# Power.net
KiCad netlist of a schematic drawn in Altium Designer
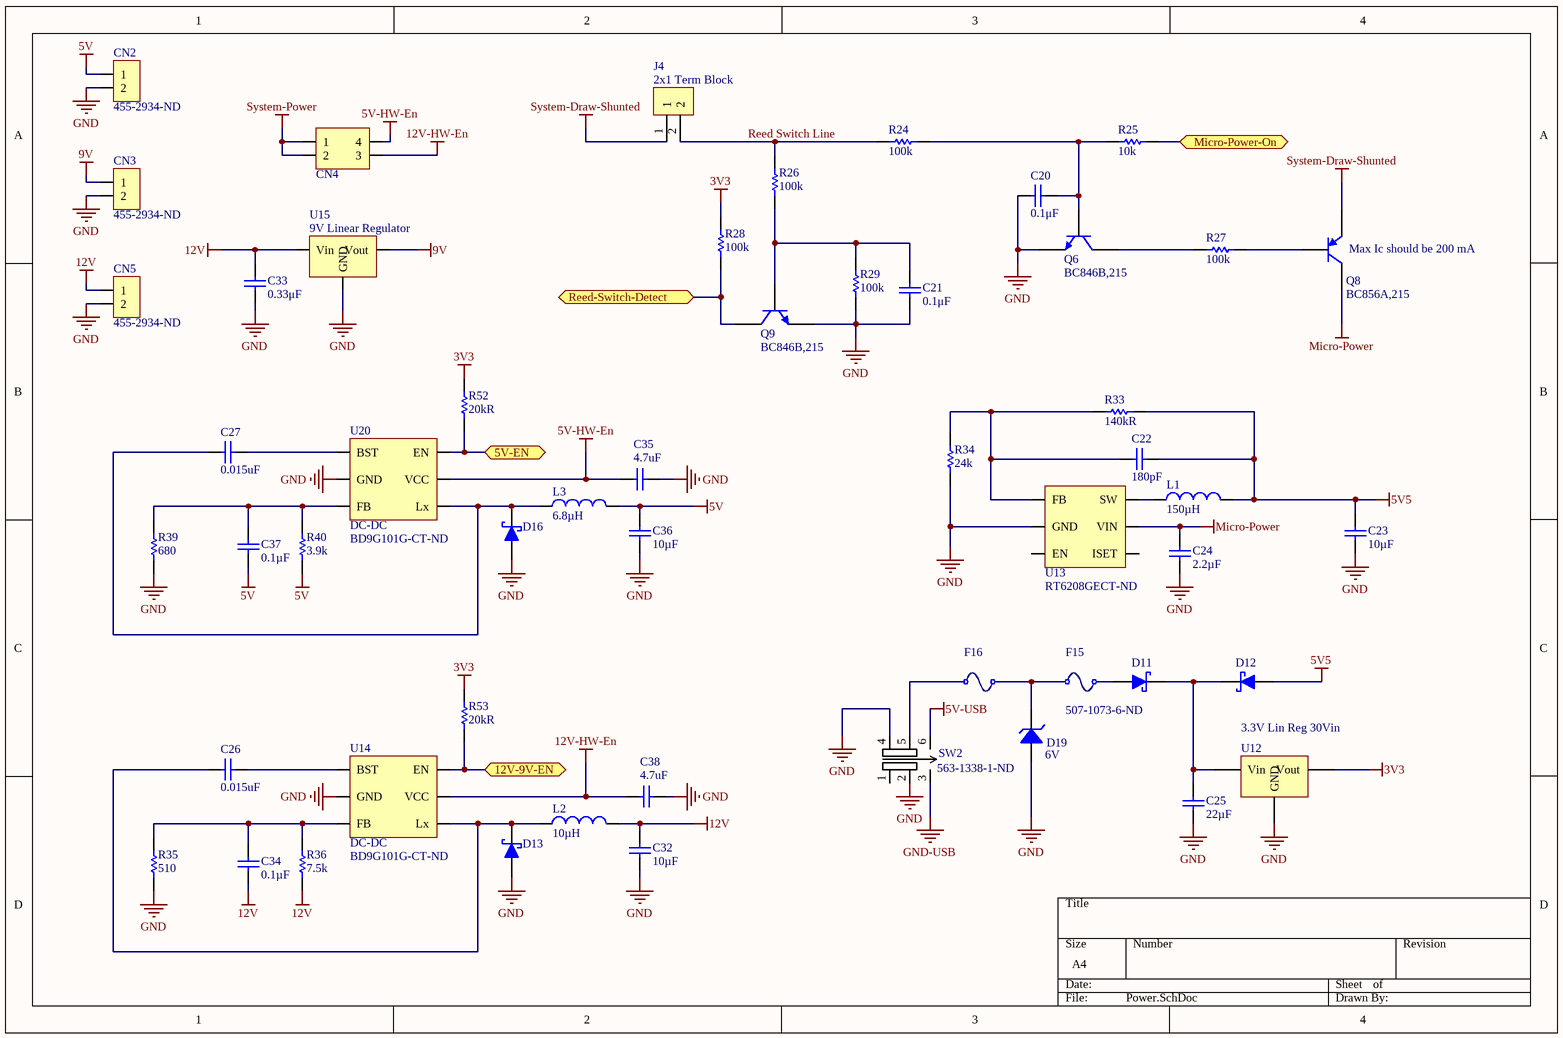
[diagram p0: Power.SchDoc]

(export (version "E")
  (design (tool "Eeschema 10.0.6"))
  (components
    (comp (ref "C20")
      (value "0.1μF")
      (footprint "CAPC1608N(0603\")")
      (description "Capacitor, Ceramic, 100V, +/- 10%, 0603 SMD, X7R")
      (fields
        (field (name "MFG") "TDK")
        (field (name "PUBLISHER") "AUVic")
        (field (name "CREATED BY") "Ashwin Sira")
      )
      (libsource (lib "AUVic_Integrated_Library_Capacitors") (part "0.1uF 100V 0603 SMD, Ceramic"))
    )
    (comp (ref "C21")
      (value "0.1μF")
      (footprint "CAPC1608N(0603\")")
      (description "Capacitor, Ceramic, 100V, +/- 10%, 0603 SMD, X7R")
      (fields
        (field (name "MFG") "TDK")
        (field (name "PUBLISHER") "AUVic")
        (field (name "CREATED BY") "Ashwin Sira")
      )
      (libsource (lib "AUVic_Integrated_Library_Capacitors") (part "0.1uF 100V 0603 SMD, Ceramic"))
    )
    (comp (ref "C22")
      (value "180pF")
      (footprint "CAPC1608N(0603\")")
      (description "Capacitor, Ceramic, 50V, +/-5%, 0603 SMD, NP0")
      (fields (field (name "CREATED BY") "Lyden Smith"))
      (libsource (lib "AUVic_Integrated_Library_Capacitors") (part "180pF 50V 0603 SMD, Ceramic"))
    )
    (comp (ref "C23")
      (value "10µF")
      (footprint "CAPC2012N(0805\")")
      (description "Capacitor, Ceramic, 10V, +/- 10%, 0805 SMD, X5R")
      (fields (field (name "PUBLISHER") "AUVic") (field (name "MADE BY") "Andy Bates"))
      (libsource (lib "AUVic_Integrated_Library_Capacitors") (part "10uF 10V 0805 SMD, Ceramic"))
    )
    (comp (ref "C24")
      (value "2.2µF")
      (footprint "CAPC1608N(0603\")")
      (description "Capacitor, Ceramic, 50V, 10%, 0603 SMD, X5R")
      (fields (field (name "MADE BY") "*") (field (name "PUBLISHER") "AUVic"))
      (libsource (lib "AUVic_Integrated_Library_Capacitors") (part "2.2uF, 50V, 0603 SMD, X5R, Ceramic"))
    )
    (comp (ref "C25")
      (value "22µF")
      (footprint "CAPC2012N(0805\")")
      (description "Capacitor, Ceramic, 35V, +/- 20%, 0805 SMD, X5R")
      (fields (field (name "PUBLISHER") "AUVic"))
      (libsource (lib "AUVic_Integrated_Library_Capacitors") (part "22uF 35V 0805 SMD, Ceramic"))
    )
    (comp (ref "C26")
      (value "0.015uF")
      (footprint "CAPC1608N(0603\")")
      (description "Capacitor, Ceramic, 50V, +/-10%, 0603 SMD, X7R")
      (fields (field (name "CREATED BY") "Lyden Smith"))
      (libsource (lib "AUVic_Integrated_Library_Capacitors") (part "0.015uF 50V 0603 SMD, Ceramic"))
    )
    (comp (ref "C27")
      (value "0.015uF")
      (footprint "CAPC1608N(0603\")")
      (description "Capacitor, Ceramic, 50V, +/-10%, 0603 SMD, X7R")
      (fields (field (name "CREATED BY") "Lyden Smith"))
      (libsource (lib "AUVic_Integrated_Library_Capacitors") (part "0.015uF 50V 0603 SMD, Ceramic"))
    )
    (comp (ref "C32")
      (value "10µF")
      (footprint "CAPC3216N(1206\")")
      (description "Capacitor, Ceramic, 50V, +/- 10%, 1206 SMD, X5R")
      (fields (field (name "PUBLISHER") "AUVic"))
      (libsource (lib "AUVic_Integrated_Library_Capacitors") (part "10uF 50V 1206 SMD, Ceramic"))
    )
    (comp (ref "C33")
      (value "0.33μF")
      (footprint "CAPC1608N(0603\")")
      (description "Capacitor, Ceramic, 50V, +/- 10%, 0603 SMD, X5R")
      (fields
        (field (name "MFG") "TDK")
        (field (name "PUBLISHER") "AUVic")
        (field (name "CREATED BY") "Andy Bates")
      )
      (libsource (lib "AUVic_Integrated_Library_Capacitors") (part "0.33uF 50V 0603 SMD, Ceramic"))
    )
    (comp (ref "C34")
      (value "0.1uF, 50V, 10%, X7R, 1608")
      (footprint "CAPC1608N(0603\")")
      (description "CAP CER 0.1UF 50V 10% X7R 1608 (0603)")
      (fields
        (field (name "MANUFACTURER") "Samsung Electro-Mechanics America, Inc")
        (field (name "MANUFACTURER PART NUMBER") "CL10B104KB8SFNC")
        (field (name "CAPACITANCE") "0.1µF")
      )
      (libsource (lib "AUVic_Integrated_Library_Capacitors") (part "0.1uF, 50V, 10%, X7R, 1608"))
    )
    (comp (ref "C35")
      (value "4.7uF")
      (footprint "CAPC3216N(1206\")")
      (description "Capacitor, Ceramic, 50V, +/- 10%, 1206 SMD, X7R")
      (fields (field (name "CREATED BY") "Lyden Smith"))
      (libsource (lib "AUVic_Integrated_Library_Capacitors") (part "4.7uF 50V 1206 SMD, Ceramic"))
    )
    (comp (ref "C36")
      (value "10µF")
      (footprint "CAPC2012N(0805\")")
      (description "Capacitor, Ceramic, 10V, +/- 10%, 0805 SMD, X5R")
      (fields (field (name "PUBLISHER") "AUVic") (field (name "MADE BY") "Andy Bates"))
      (libsource (lib "") (part "10uF 10V 0805 SMD, Ceramic_1"))
    )
    (comp (ref "C37")
      (value "0.1uF, 50V, 10%, X7R, 1608")
      (footprint "CAPC1608N(0603\")")
      (description "CAP CER 0.1UF 50V 10% X7R 1608 (0603)")
      (fields
        (field (name "MANUFACTURER") "Samsung Electro-Mechanics America, Inc")
        (field (name "MANUFACTURER PART NUMBER") "CL10B104KB8SFNC")
        (field (name "CAPACITANCE") "0.1µF")
      )
      (libsource (lib "AUVic_Integrated_Library_Capacitors") (part "0.1uF, 50V, 10%, X7R, 1608"))
    )
    (comp (ref "C38")
      (value "4.7uF")
      (footprint "CAPC3216N(1206\")")
      (description "Capacitor, Ceramic, 50V, +/- 10%, 1206 SMD, X7R")
      (fields (field (name "CREATED BY") "Lyden Smith"))
      (libsource (lib "AUVic_Integrated_Library_Capacitors") (part "4.7uF 50V 1206 SMD, Ceramic"))
    )
    (comp (ref "CN2")
      (value "1x2, JST B2B-EH-A, Pads Pitch: 0.098\" (2.50mm), Through Hole")
      (footprint "Male JST B2B-EH-A")
      (fields (field (name "SUPPLIER PART NUMBER 1") "455-2934-ND") (field (name "CREATED BY") "Lyden Smith"))
      (libsource (lib "AUVic_Integrated_Library_Connectors") (part "1x2, JST B2B-EH-A, Pads Pitch{colon} 0.098{dblquote} (2.50mm), Through Hole"))
    )
    (comp (ref "CN3")
      (value "1x2, JST B2B-EH-A, Pads Pitch: 0.098\" (2.50mm), Through Hole")
      (footprint "Male JST B2B-EH-A")
      (fields (field (name "SUPPLIER PART NUMBER 1") "455-2934-ND") (field (name "CREATED BY") "Lyden Smith"))
      (libsource (lib "AUVic_Integrated_Library_Connectors") (part "1x2, JST B2B-EH-A, Pads Pitch{colon} 0.098{dblquote} (2.50mm), Through Hole"))
    )
    (comp (ref "CN4")
      (value "Header, Male, 2x2, Pitch: 0.1\" (2.54mm), THT")
      (footprint "Header, Male, 2x2, Pitch: 0.1\" (2.54mm),THT")
      (fields
        (field (name "PUBLISHER") "AUVic")
        (field (name "REVIEWED BY") "*")
        (field (name "CREATED BY") "Lyden Smith")
      )
      (libsource (lib "AUVic_Integrated_Library_Connectors") (part "Header, Male, 2x2, Pitch{colon} 0.1{dblquote} (2.54mm), THT"))
    )
    (comp (ref "CN5")
      (value "1x2, JST B2B-EH-A, Pads Pitch: 0.098\" (2.50mm), Through Hole")
      (footprint "Male JST B2B-EH-A")
      (fields (field (name "SUPPLIER PART NUMBER 1") "455-2934-ND") (field (name "CREATED BY") "Lyden Smith"))
      (libsource (lib "AUVic_Integrated_Library_Connectors") (part "1x2, JST B2B-EH-A, Pads Pitch{colon} 0.098{dblquote} (2.50mm), Through Hole"))
    )
    (comp (ref "D11")
      (value "CUS08F30H3FCT-ND")
      (footprint "SC-76")
      (description "Diode, Schottky, 30V, 800mA")
      (fields (field (name "CREATED BY") "Andy Bates") (field (name "PUBLISHER") "AUVic"))
      (libsource (lib "AUVic_Integrated_Library_Diodes") (part "CUS08F30H3FCT-ND"))
    )
    (comp (ref "D12")
      (value "CUS08F30H3FCT-ND")
      (footprint "SC-76")
      (description "Diode, Schottky, 30V, 800mA")
      (fields (field (name "CREATED BY") "Andy Bates") (field (name "PUBLISHER") "AUVic"))
      (libsource (lib "AUVic_Integrated_Library_Diodes") (part "CUS08F30H3FCT-ND"))
    )
    (comp (ref "D13")
      (value "RB060M-60TR")
      (footprint "SOD-123")
      (description "Diode, Schottky, 60V, 2A")
      (fields (field (name "CREATED BY") "Lyden Smith"))
      (libsource (lib "AUVic_Integrated_Library_Diodes") (part "RB060M-60TR"))
    )
    (comp (ref "D16")
      (value "RB060M-60TR")
      (footprint "SOD-123")
      (description "Diode, Schottky, 60V, 2A")
      (fields (field (name "CREATED BY") "Lyden Smith"))
      (libsource (lib "AUVic_Integrated_Library_Diodes") (part "RB060M-60TR"))
    )
    (comp (ref "D19")
      (value "6V")
      (footprint "DO-214AA")
      (description "DIODE ZENER 6V 5W DO214AA")
      (fields (field (name "CREATED BY") "Lyden Smith"))
      (libsource (lib "AUVic_Integrated_Library_Diodes") (part "SMBJ5340B-TPMSCT-ND"))
    )
    (comp (ref "F15")
      (value "SMD")
      (footprint "1206 SMD")
      (description "SMD Fuse, 250mA, 63V, 1206")
      (fields
        (field (name "SUPPLIER PART NUMBER 1") "507-1073-6-ND")
        (field (name "CREATED BY") "Lyden Smith")
      )
      (libsource (lib "AUVic_Integrated_Library_Fuses") (part "SMD Fuse, 250mA, 63V, 1206"))
    )
    (comp (ref "F16")
      (value "SMD")
      (footprint "1206 SMD")
      (description "SMD Fuse, 250mA, 63V, 1206")
      (fields (field (name "CREATED BY") "Lyden Smith"))
      (libsource (lib "AUVic_Integrated_Library_Fuses") (part "SMD Fuse, 250mA, 63V, 1206"))
    )
    (comp (ref "J4")
      (value "2x1 Term Block")
      (footprint "2X1 Terminal Blocks")
      (fields (field (name "MADE BY") "Andy Bates"))
      (libsource (lib "AUVic_Integrated_Library_Connectors") (part "2x1 Terminal Block"))
    )
    (comp (ref "L1")
      (value "150µH")
      (footprint "CB - 1007 (2518)")
      (description "150µH 210mA 4.6Ohm")
      (fields (field (name "CREATED BY") "Lyden Smith"))
      (libsource (lib "AUVic_Integrated_Library_Inductors") (part "CB2518T151K"))
    )
    (comp (ref "L2")
      (value "10µH")
      (footprint "NR4018T6R8M Inductor")
      (description "10uH 840mA")
      (fields (field (name "CREATED BY") "Lyden Smith"))
      (libsource (lib "AUVic_Integrated_Library_Inductors") (part "NR4018T100M"))
    )
    (comp (ref "L3")
      (value "6.8µH")
      (footprint "NR4018T6R8M Inductor")
      (description "6.8uH 1.06A")
      (fields (field (name "CREATED BY") "Lyden Smith"))
      (libsource (lib "AUVic_Integrated_Library_Inductors") (part "NR4018T6R8M"))
    )
    (comp (ref "Q6")
      (value "BC846B,215")
      (footprint "SOT-23")
      (description "NPN 65V 100mA 250mW")
      (fields (field (name "PUBLISHER") "Andy Bates"))
      (libsource (lib "AUVic_Integrated_Library_Transistors") (part "BC846B,215"))
    )
    (comp (ref "Q8")
      (value "BC856A,215")
      (footprint "SOT-23")
      (description "PNP 65V 100mA 250mW")
      (libsource (lib "AUVic_Integrated_Library_Transistors") (part "BC856A,215"))
    )
    (comp (ref "Q9")
      (value "BC846B,215")
      (footprint "SOT-23")
      (description "NPN 65V 100mA 250mW")
      (fields (field (name "PUBLISHER") "Andy Bates"))
      (libsource (lib "AUVic_Integrated_Library_Transistors") (part "BC846B,215"))
    )
    (comp (ref "R24")
      (value "100k")
      (footprint "RESC1608N(0603\")")
      (description "100kR, 1%, 1/10W, 0603 SMD")
      (fields (field (name "MADE BY") "Andy Bates"))
      (libsource (lib "AUVic_Integrated_Library_Resistors") (part "100kR, 1%, 1/10W, 0603 SMD"))
    )
    (comp (ref "R25")
      (value "10k")
      (footprint "RESC1608N(0603\")")
      (description "10kR, 1%, 1/10W, 0603 SMD")
      (fields (field (name "MADE BY") "Ashwin Sira"))
      (libsource (lib "AUVic_Integrated_Library_Resistors") (part "10kR, 1%, 1/10W, 0603 SMD"))
    )
    (comp (ref "R26")
      (value "100k")
      (footprint "RESC1608N(0603\")")
      (description "100kR, 1%, 1/10W, 0603 SMD")
      (fields (field (name "MADE BY") "Andy Bates"))
      (libsource (lib "AUVic_Integrated_Library_Resistors") (part "100kR, 1%, 1/10W, 0603 SMD"))
    )
    (comp (ref "R27")
      (value "100k")
      (footprint "RESC1608N(0603\")")
      (description "100kR, 1%, 1/10W, 0603 SMD")
      (fields (field (name "MADE BY") "Andy Bates"))
      (libsource (lib "AUVic_Integrated_Library_Resistors") (part "100kR, 1%, 1/10W, 0603 SMD"))
    )
    (comp (ref "R28")
      (value "100k")
      (footprint "RESC1608N(0603\")")
      (description "100kR, 1%, 1/10W, 0603 SMD")
      (fields (field (name "MADE BY") "Andy Bates"))
      (libsource (lib "AUVic_Integrated_Library_Resistors") (part "100kR, 1%, 1/10W, 0603 SMD"))
    )
    (comp (ref "R29")
      (value "100k")
      (footprint "RESC1608N(0603\")")
      (description "100kR, 1%, 1/10W, 0603 SMD")
      (fields (field (name "MADE BY") "Andy Bates"))
      (libsource (lib "AUVic_Integrated_Library_Resistors") (part "100kR, 1%, 1/10W, 0603 SMD"))
    )
    (comp (ref "R33")
      (value "140kR")
      (footprint "RESC1005N(0402\")")
      (description "140kR, 1%, 1/16W, 0402, SMD")
      (fields (field (name "CREATED BY") "Lyden Smith") (field (name "PUBLISHER") "AUVic"))
      (libsource (lib "AUVic_Integrated_Library_Resistors") (part "140kR, 1%, 1/16W, 0402, SMD"))
    )
    (comp (ref "R34")
      (value "24k")
      (footprint "RESC2012N(0805\")")
      (description "24k, 5%, 1/8W, 0805 SMD")
      (fields (field (name "CREATED BY") "Lyden Smith"))
      (libsource (lib "AUVic_Integrated_Library_Resistors") (part "24k, 5%, 1/8W, 0805 SMD"))
    )
    (comp (ref "R35")
      (value "510")
      (footprint "RESC2012N(0805\")")
      (description "510, 5%, 1/8W, 0805 SMD")
      (fields (field (name "CREATED BY") "Lyden Smith"))
      (libsource (lib "AUVic_Integrated_Library_Resistors") (part "510, 5%, 1/8W, 0805 SMD"))
    )
    (comp (ref "R36")
      (value "7.5k")
      (footprint "RESC2012N(0805\")")
      (description "7.5k, 5%, 1/8W, 0805 SMD")
      (fields (field (name "CREATED BY") "Lyden Smith"))
      (libsource (lib "AUVic_Schematic_Library_Resistors") (part "7.5k, 5%, 1/8W, 0805 SMD"))
    )
    (comp (ref "R39")
      (value "680")
      (footprint "RESC2012N(0805\")")
      (description "680, 5%, 1/8W, 0805 SMD")
      (fields (field (name "CREATED BY") "Lyden Smith"))
      (libsource (lib "AUVic_Integrated_Library_Resistors") (part "680, 5%, 1/8W, 0805 SMD"))
    )
    (comp (ref "R40")
      (value "3.9k")
      (footprint "RESC2012N(0805\")")
      (description "3.9k, 5%, 1/8W, 0805 SMD")
      (fields (field (name "CREATED BY") "Lyden Smith"))
      (libsource (lib "AUVic_Integrated_Library_Resistors") (part "3.9k, 5%, 1/8W, 0805 SMD"))
    )
    (comp (ref "R52")
      (value "20kR")
      (footprint "RESC1608N(0603\")")
      (description "20k, 1%, 1/10W, 0603, SMD")
      (fields (field (name "CREATED BY") "Andy Bates") (field (name "PUBLISHER") "AUVic"))
      (libsource (lib "AUVic_Integrated_Library_Resistors") (part "20k, 1%, 1/10W, 0603, SMD"))
    )
    (comp (ref "R53")
      (value "20kR")
      (footprint "RESC1608N(0603\")")
      (description "20k, 1%, 1/10W, 0603, SMD")
      (fields (field (name "CREATED BY") "Andy Bates") (field (name "PUBLISHER") "AUVic"))
      (libsource (lib "AUVic_Integrated_Library_Resistors") (part "20k, 1%, 1/10W, 0603, SMD"))
    )
    (comp (ref "SW2")
      (value "*")
      (footprint "CL-2B-22A")
      (description "DPDT, 12V, 200mA, SMT")
      (fields
        (field (name "SUPPLIER PART NUMBER 1") "563-1338-1-ND")
        (field (name "CREATED BY") "Lyden Smith")
      )
      (libsource (lib "AUVic_Integrated_Library_Switches") (part "DPDT, 12V, 200mA, SMT"))
    )
    (comp (ref "U12")
      (value "3.3V Lin Reg 30Vin")
      (footprint "T0-252")
      (libsource (lib "AUVic_Integrated_Library_Regulators") (part "3.3V TO-252 Linear Regulator"))
    )
    (comp (ref "U13")
      (value "RT6208GE")
      (footprint "SOT23-6_L")
      (description "Adjustable Buck, 100mA, SOT-23")
      (fields
        (field (name "SUPPLIER PART NUMBER 1") "RT6208GECT-ND")
        (field (name "CREATED BY") "Lyden Smith")
      )
      (libsource (lib "AUVic_Integrated_Library_Regulators") (part "RT6208GE"))
    )
    (comp (ref "U14")
      (value "DC-DC")
      (footprint "SOT23-6_L")
      (description "DC-DC Regulator, 6V-42V in, 1V-29.4V out, 500mA")
      (fields (field (name "SUPPLIER PART NUMBER 1") "BD9G101G-CT-ND"))
      (libsource (lib "AUVic_Integrated_Library_Regulators") (part "BD9G101G-TR"))
    )
    (comp (ref "U15")
      (value "9V Linear Regulator")
      (footprint "DPAK229P991X238-3N")
      (description "9V Linear Regulator, 500mA")
      (fields (field (name "CREATED BY") "Lyden Smith"))
      (libsource (lib "AUVic_Integrated_Library_Regulators") (part "MC78M09CDTRKG"))
    )
    (comp (ref "U20")
      (value "DC-DC")
      (footprint "SOT23-6_L")
      (description "DC-DC Regulator, 6V-42V in, 1V-29.4V out, 500mA")
      (fields (field (name "SUPPLIER PART NUMBER 1") "BD9G101G-CT-ND"))
      (libsource (lib "AUVic_Integrated_Library_Regulators") (part "BD9G101G-TR"))
    )
  )
  (nets
    (net (code "1") (name "/5V-EN") (class "Default")
      (node (ref "R52") (pin "1") (pinfunction "1_1") (pintype "passive"))
      (node (ref "U20") (pin "4") (pinfunction "EN_4") (pintype "passive"))
    )
    (net (code "2") (name "/12V-9V-EN") (class "Default")
      (node (ref "R53") (pin "1") (pinfunction "1_1") (pintype "passive"))
      (node (ref "U14") (pin "4") (pinfunction "EN_4") (pintype "passive"))
    )
    (net (code "3") (name "/Micro-Power-On") (class "Default")
      (node (ref "R25") (pin "2") (pinfunction "2_2") (pintype "passive"))
    )
    (net (code "4") (name "/Reed Switch Line") (class "Default")
      (node (ref "J4") (pin "2") (pinfunction "2_2") (pintype "passive"))
      (node (ref "R24") (pin "2") (pinfunction "2_2") (pintype "passive"))
      (node (ref "R26") (pin "2") (pinfunction "2_2") (pintype "passive"))
    )
    (net (code "5") (name "/Reed-Switch-Detect") (class "Default")
      (node (ref "Q9") (pin "3") (pinfunction "C_3") (pintype "passive"))
      (node (ref "R28") (pin "1") (pinfunction "1_1") (pintype "passive"))
    )
    (net (code "6") (name "3V3") (class "Default")
      (node (ref "R28") (pin "2") (pinfunction "2_2") (pintype "passive"))
      (node (ref "R52") (pin "2") (pinfunction "2_2") (pintype "passive"))
      (node (ref "R53") (pin "2") (pinfunction "2_2") (pintype "passive"))
      (node (ref "U12") (pin "3") (pinfunction "Vout_3") (pintype "passive"))
    )
    (net (code "7") (name "5V") (class "Default")
      (node (ref "C36") (pin "2") (pinfunction "Cathode_2") (pintype "passive"))
      (node (ref "C37") (pin "1") (pinfunction "Anode_1") (pintype "passive"))
      (node (ref "CN2") (pin "1") (pinfunction "1_1") (pintype "passive"))
      (node (ref "L3") (pin "2") (pinfunction "2_2") (pintype "passive"))
      (node (ref "R40") (pin "1") (pinfunction "1_1") (pintype "passive"))
    )
    (net (code "8") (name "5V-HW-En") (class "Default")
      (node (ref "C35") (pin "2") (pinfunction "2_2") (pintype "passive"))
      (node (ref "CN4") (pin "4") (pinfunction "4_4") (pintype "passive"))
      (node (ref "U20") (pin "5") (pinfunction "VCC_5") (pintype "power_in"))
    )
    (net (code "9") (name "5V-USB") (class "Default")
      (node (ref "SW2") (pin "6") (pinfunction "6_6") (pintype "passive"))
    )
    (net (code "10") (name "5V5") (class "Default")
      (node (ref "C22") (pin "2") (pinfunction "2_2") (pintype "passive"))
      (node (ref "C23") (pin "2") (pinfunction "Cathode_2") (pintype "passive"))
      (node (ref "D12") (pin "A") (pinfunction "Anode_A") (pintype "passive"))
      (node (ref "L1") (pin "2") (pinfunction "2_2") (pintype "passive"))
      (node (ref "R33") (pin "2") (pinfunction "2_2") (pintype "passive"))
    )
    (net (code "11") (name "9V") (class "Default")
      (node (ref "CN3") (pin "1") (pinfunction "1_1") (pintype "passive"))
      (node (ref "U15") (pin "3") (pinfunction "Vout_3") (pintype "passive"))
    )
    (net (code "12") (name "12V") (class "Default")
      (node (ref "C32") (pin "2") (pinfunction "Cathode_2") (pintype "passive"))
      (node (ref "C33") (pin "2") (pinfunction "Cathode_2") (pintype "passive"))
      (node (ref "C34") (pin "1") (pinfunction "Anode_1") (pintype "passive"))
      (node (ref "CN5") (pin "1") (pinfunction "1_1") (pintype "passive"))
      (node (ref "L2") (pin "2") (pinfunction "2_2") (pintype "passive"))
      (node (ref "R36") (pin "1") (pinfunction "1_1") (pintype "passive"))
      (node (ref "U15") (pin "1") (pinfunction "Vin_1") (pintype "passive"))
    )
    (net (code "13") (name "12V-HW-En") (class "Default")
      (node (ref "C38") (pin "2") (pinfunction "2_2") (pintype "passive"))
      (node (ref "CN4") (pin "3") (pinfunction "3_3") (pintype "passive"))
      (node (ref "U14") (pin "5") (pinfunction "VCC_5") (pintype "power_in"))
    )
    (net (code "14") (name "GND") (class "Default")
      (node (ref "C20") (pin "1") (pinfunction "Anode_1") (pintype "passive"))
      (node (ref "C21") (pin "1") (pinfunction "Anode_1") (pintype "passive"))
      (node (ref "C23") (pin "1") (pinfunction "Anode_1") (pintype "passive"))
      (node (ref "C24") (pin "1") (pinfunction "Anode_1") (pintype "passive"))
      (node (ref "C25") (pin "1") (pinfunction "Anode_1") (pintype "passive"))
      (node (ref "C32") (pin "1") (pinfunction "Anode_1") (pintype "passive"))
      (node (ref "C33") (pin "1") (pinfunction "Anode_1") (pintype "passive"))
      (node (ref "C35") (pin "1") (pinfunction "1_1") (pintype "passive"))
      (node (ref "C36") (pin "1") (pinfunction "Anode_1") (pintype "passive"))
      (node (ref "C38") (pin "1") (pinfunction "1_1") (pintype "passive"))
      (node (ref "CN2") (pin "2") (pinfunction "2_2") (pintype "passive"))
      (node (ref "CN3") (pin "2") (pinfunction "2_2") (pintype "passive"))
      (node (ref "CN5") (pin "2") (pinfunction "2_2") (pintype "passive"))
      (node (ref "D13") (pin "A") (pinfunction "Anode_A") (pintype "passive"))
      (node (ref "D16") (pin "A") (pinfunction "Anode_A") (pintype "passive"))
      (node (ref "D19") (pin "A") (pinfunction "Anode_A") (pintype "passive"))
      (node (ref "Q6") (pin "2") (pinfunction "E_2") (pintype "passive"))
      (node (ref "Q9") (pin "2") (pinfunction "E_2") (pintype "passive"))
      (node (ref "R29") (pin "1") (pinfunction "1_1") (pintype "passive"))
      (node (ref "R34") (pin "1") (pinfunction "1_1") (pintype "passive"))
      (node (ref "R35") (pin "1") (pinfunction "1_1") (pintype "passive"))
      (node (ref "R39") (pin "1") (pinfunction "1_1") (pintype "passive"))
      (node (ref "SW2") (pin "2") (pinfunction "2_2") (pintype "passive"))
      (node (ref "SW2") (pin "4") (pinfunction "4_4") (pintype "passive"))
      (node (ref "U12") (pin "1") (pinfunction "GND_1") (pintype "passive"))
      (node (ref "U13") (pin "2") (pinfunction "GND_2") (pintype "passive"))
      (node (ref "U14") (pin "2") (pinfunction "GND_2") (pintype "power_in"))
      (node (ref "U15") (pin "4") (pinfunction "GND_4") (pintype "passive"))
      (node (ref "U20") (pin "2") (pinfunction "GND_2") (pintype "power_in"))
    )
    (net (code "15") (name "GND-USB") (class "Default")
      (node (ref "SW2") (pin "3") (pinfunction "3_3") (pintype "passive"))
    )
    (net (code "16") (name "Micro-Power") (class "Default")
      (node (ref "C24") (pin "2") (pinfunction "Cathode_2") (pintype "passive"))
      (node (ref "Q8") (pin "3") (pinfunction "C_3") (pintype "passive"))
      (node (ref "U13") (pin "5") (pinfunction "VIN_5") (pintype "passive"))
    )
    (net (code "17") (name "Net-(C20-Cathode)") (class "Default")
      (node (ref "C20") (pin "2") (pinfunction "Cathode_2") (pintype "passive"))
      (node (ref "Q6") (pin "1") (pinfunction "B_1") (pintype "passive"))
      (node (ref "R24") (pin "1") (pinfunction "1_1") (pintype "passive"))
      (node (ref "R25") (pin "1") (pinfunction "1_1") (pintype "passive"))
    )
    (net (code "18") (name "Net-(C21-Cathode)") (class "Default")
      (node (ref "C21") (pin "2") (pinfunction "Cathode_2") (pintype "passive"))
      (node (ref "Q9") (pin "1") (pinfunction "B_1") (pintype "passive"))
      (node (ref "R26") (pin "1") (pinfunction "1_1") (pintype "passive"))
      (node (ref "R29") (pin "2") (pinfunction "2_2") (pintype "passive"))
    )
    (net (code "19") (name "Net-(C25-Cathode)") (class "Default")
      (node (ref "C25") (pin "2") (pinfunction "Cathode_2") (pintype "passive"))
      (node (ref "D11") (pin "K") (pinfunction "Cathode_K") (pintype "passive"))
      (node (ref "D12") (pin "K") (pinfunction "Cathode_K") (pintype "passive"))
      (node (ref "U12") (pin "2") (pinfunction "Vin_2") (pintype "passive"))
    )
    (net (code "20") (name "Net-(C34-Cathode)") (class "Default")
      (node (ref "C34") (pin "2") (pinfunction "Cathode_2") (pintype "passive"))
      (node (ref "R35") (pin "2") (pinfunction "2_2") (pintype "passive"))
      (node (ref "R36") (pin "2") (pinfunction "2_2") (pintype "passive"))
      (node (ref "U14") (pin "3") (pinfunction "FB_3") (pintype "power_in"))
    )
    (net (code "21") (name "Net-(C37-Cathode)") (class "Default")
      (node (ref "C37") (pin "2") (pinfunction "Cathode_2") (pintype "passive"))
      (node (ref "R39") (pin "2") (pinfunction "2_2") (pintype "passive"))
      (node (ref "R40") (pin "2") (pinfunction "2_2") (pintype "passive"))
      (node (ref "U20") (pin "3") (pinfunction "FB_3") (pintype "power_in"))
    )
    (net (code "22") (name "Net-(D11-Anode)") (class "Default")
      (node (ref "D11") (pin "A") (pinfunction "Anode_A") (pintype "passive"))
      (node (ref "F15") (pin "2") (pinfunction "2_2") (pintype "passive"))
    )
    (net (code "23") (name "Net-(D13-Cathode)") (class "Default")
      (node (ref "C26") (pin "1") (pinfunction "1_1") (pintype "passive"))
      (node (ref "D13") (pin "K") (pinfunction "Cathode_K") (pintype "passive"))
      (node (ref "L2") (pin "1") (pinfunction "1_1") (pintype "passive"))
      (node (ref "U14") (pin "6") (pinfunction "Lx_6") (pintype "power_in"))
    )
    (net (code "24") (name "Net-(D16-Cathode)") (class "Default")
      (node (ref "C27") (pin "1") (pinfunction "1_1") (pintype "passive"))
      (node (ref "D16") (pin "K") (pinfunction "Cathode_K") (pintype "passive"))
      (node (ref "L3") (pin "1") (pinfunction "1_1") (pintype "passive"))
      (node (ref "U20") (pin "6") (pinfunction "Lx_6") (pintype "power_in"))
    )
    (net (code "25") (name "Net-(D19-Cathode)") (class "Default")
      (node (ref "D19") (pin "K") (pinfunction "Cathode_K") (pintype "passive"))
      (node (ref "F15") (pin "1") (pinfunction "1_1") (pintype "passive"))
      (node (ref "F16") (pin "2") (pinfunction "2_2") (pintype "passive"))
    )
    (net (code "26") (name "Net-(F16-Pad1)") (class "Default")
      (node (ref "F16") (pin "1") (pinfunction "1_1") (pintype "passive"))
      (node (ref "SW2") (pin "5") (pinfunction "5_5") (pintype "passive"))
    )
    (net (code "27") (name "Net-(Q6-C)") (class "Default")
      (node (ref "Q6") (pin "3") (pinfunction "C_3") (pintype "passive"))
      (node (ref "R27") (pin "1") (pinfunction "1_1") (pintype "passive"))
    )
    (net (code "28") (name "Net-(Q8-B)") (class "Default")
      (node (ref "Q8") (pin "1") (pinfunction "B_1") (pintype "passive"))
      (node (ref "R27") (pin "2") (pinfunction "2_2") (pintype "passive"))
    )
    (net (code "29") (name "Net-(U13-FB)") (class "Default")
      (node (ref "C22") (pin "1") (pinfunction "1_1") (pintype "passive"))
      (node (ref "R33") (pin "1") (pinfunction "1_1") (pintype "passive"))
      (node (ref "R34") (pin "2") (pinfunction "2_2") (pintype "passive"))
      (node (ref "U13") (pin "1") (pinfunction "FB_1") (pintype "passive"))
    )
    (net (code "30") (name "Net-(U13-SW)") (class "Default")
      (node (ref "L1") (pin "1") (pinfunction "1_1") (pintype "passive"))
      (node (ref "U13") (pin "6") (pinfunction "SW_6") (pintype "passive"))
    )
    (net (code "31") (name "Net-(U14-BST)") (class "Default")
      (node (ref "C26") (pin "2") (pinfunction "2_2") (pintype "passive"))
      (node (ref "U14") (pin "1") (pinfunction "BST_1") (pintype "power_in"))
    )
    (net (code "32") (name "Net-(U20-BST)") (class "Default")
      (node (ref "C27") (pin "2") (pinfunction "2_2") (pintype "passive"))
      (node (ref "U20") (pin "1") (pinfunction "BST_1") (pintype "power_in"))
    )
    (net (code "33") (name "System-Draw-Shunted") (class "Default")
      (node (ref "J4") (pin "1") (pinfunction "1_1") (pintype "passive"))
      (node (ref "Q8") (pin "2") (pinfunction "E_2") (pintype "passive"))
    )
    (net (code "34") (name "System-Power") (class "Default")
      (node (ref "CN4") (pin "1") (pinfunction "1_1") (pintype "passive"))
      (node (ref "CN4") (pin "2") (pinfunction "2_2") (pintype "passive"))
    )
    (net (code "35") (name "unconnected-(SW2-Pad1)") (class "Default")
      (node (ref "SW2") (pin "1") (pinfunction "1_1") (pintype "passive"))
    )
    (net (code "36") (name "unconnected-(U13-EN-Pad3)") (class "Default")
      (node (ref "U13") (pin "3") (pinfunction "EN_3") (pintype "passive"))
    )
    (net (code "37") (name "unconnected-(U13-ISET-Pad4)") (class "Default")
      (node (ref "U13") (pin "4") (pinfunction "ISET_4") (pintype "passive"))
    )
  )
)
